# M405B.net
KiCad netlist of a schematic drawn in EAGLE
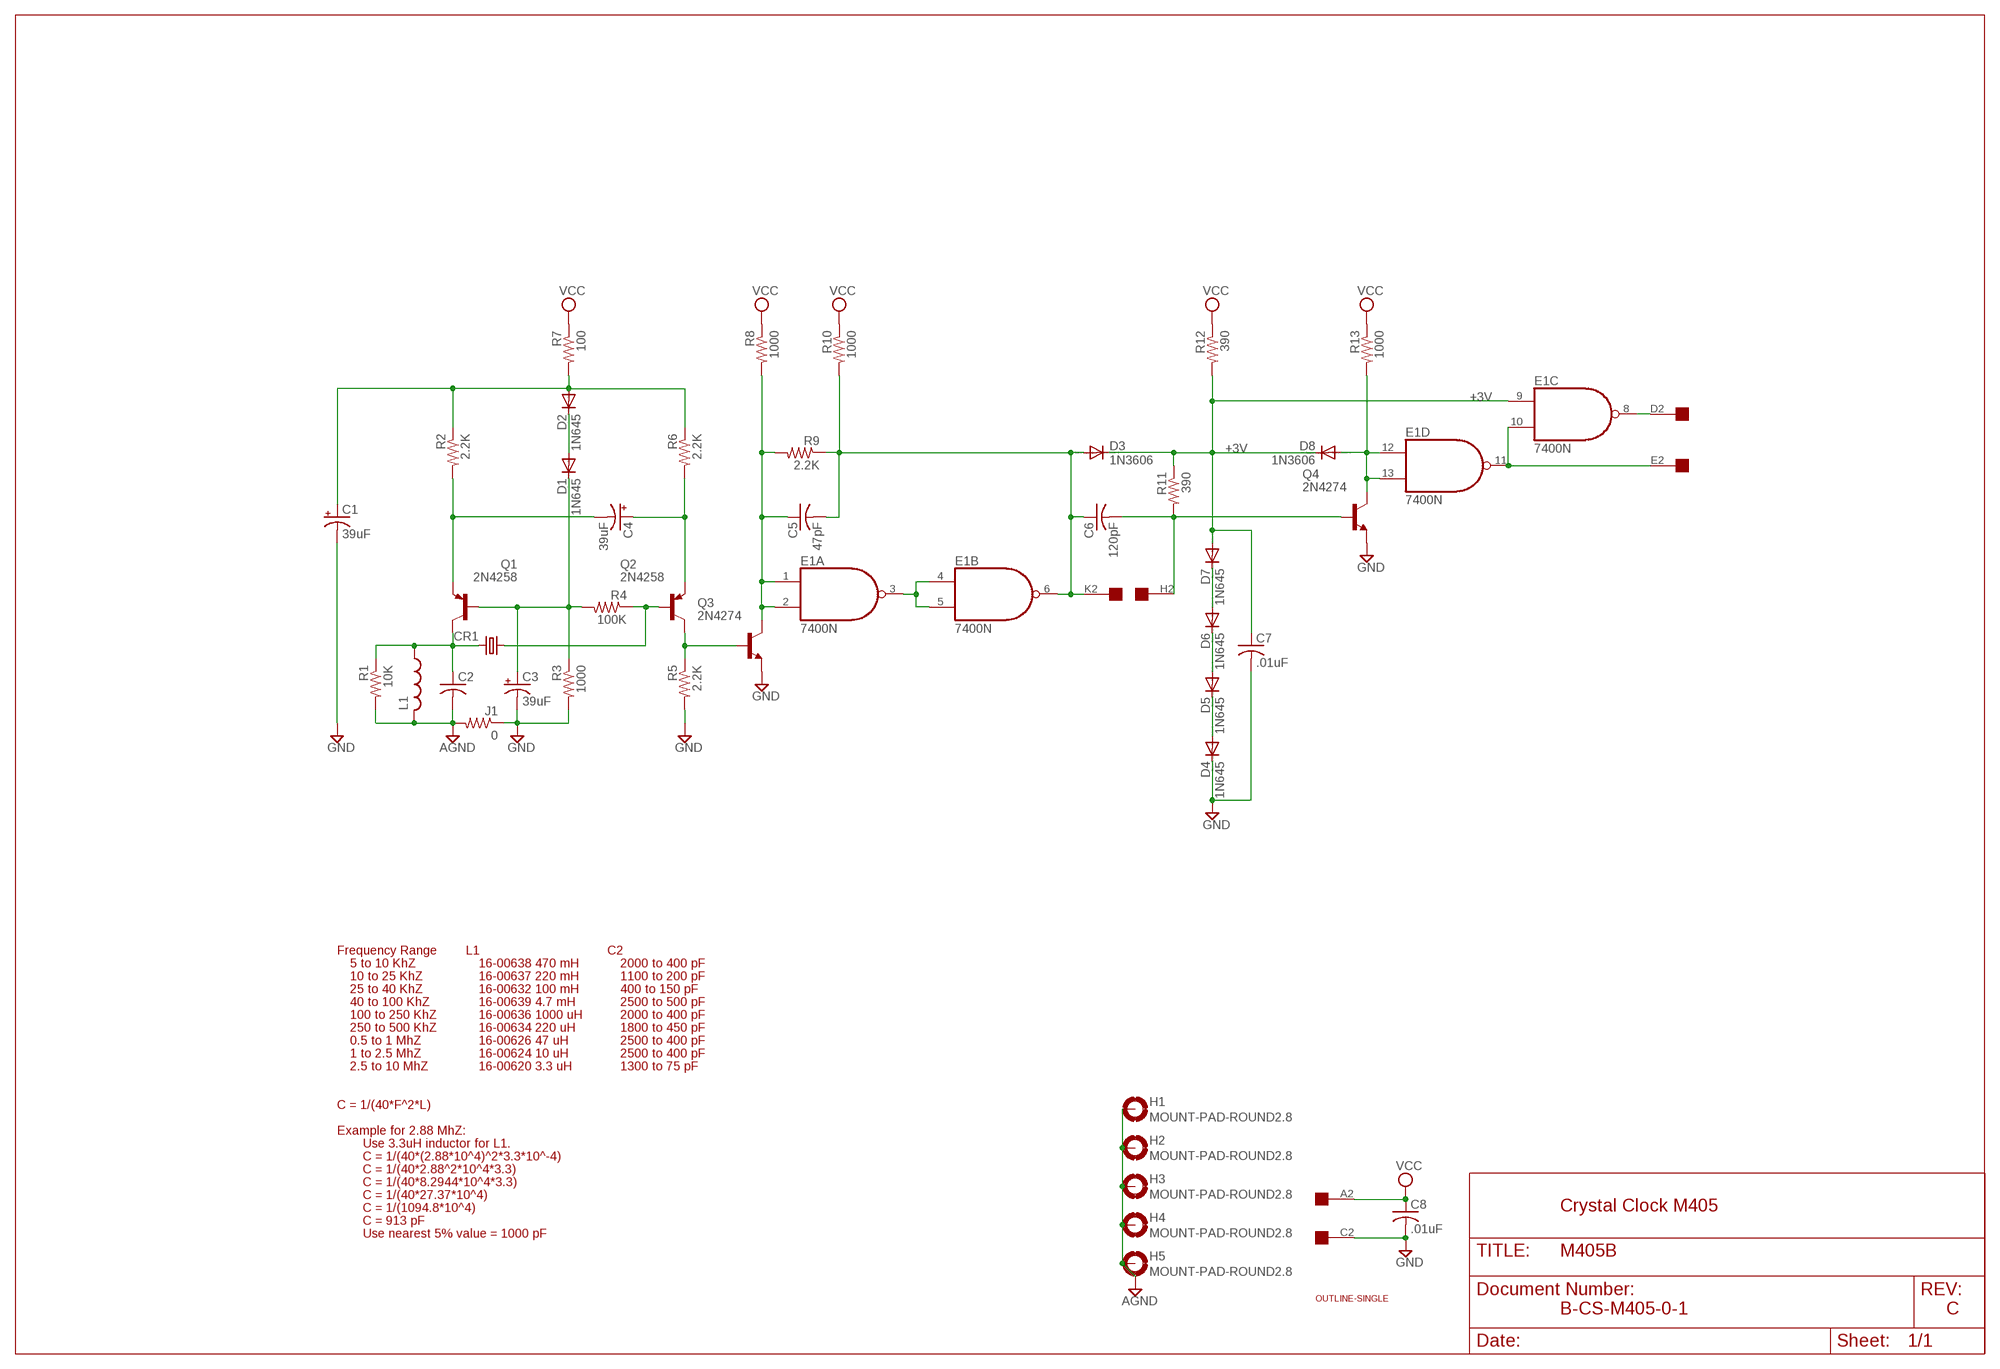
[diagram p0: schematic, sheet 1]

(export (version "E")
  (design (tool "Eeschema 10.0.6"))
  (components
    (comp (ref "C1")
      (value "39uF")
      (footprint "eagle-import:E15-5")
      (libsource (lib "eagle-import") (part "CPOL-USE15-5AXIAL"))
    )
    (comp (ref "C2")
      (value "C-US150-054X183")
      (footprint "eagle-import:C150-054X183")
      (libsource (lib "eagle-import") (part "C-US150-054X183"))
    )
    (comp (ref "C3")
      (value "39uF")
      (footprint "eagle-import:E15-5")
      (libsource (lib "eagle-import") (part "CPOL-USE15-5AXIAL"))
    )
    (comp (ref "C4")
      (value "39uF")
      (footprint "eagle-import:E15-5")
      (libsource (lib "eagle-import") (part "CPOL-USE15-5AXIAL"))
    )
    (comp (ref "C5")
      (value "47pF")
      (footprint "eagle-import:C050-025X075")
      (libsource (lib "eagle-import") (part "C-US050-025X075"))
    )
    (comp (ref "C6")
      (value "120pF")
      (footprint "eagle-import:C050-025X075")
      (libsource (lib "eagle-import") (part "C-US050-025X075"))
    )
    (comp (ref "C7")
      (value ".01uF")
      (footprint "eagle-import:C050-025X075")
      (libsource (lib "eagle-import") (part "C-US050-025X075"))
    )
    (comp (ref "C8")
      (value ".01uF")
      (footprint "eagle-import:C050-025X075")
      (libsource (lib "eagle-import") (part "C-US050-025X075"))
    )
    (comp (ref "CR1")
      (value "CRYSTALHC13U-H")
      (footprint "eagle-import:HC13U-H")
      (libsource (lib "eagle-import") (part "CRYSTALHC13U-H"))
    )
    (comp (ref "D1")
      (value "1N645")
      (footprint "eagle-import:DO35-10")
      (libsource (lib "eagle-import") (part "1N4148DO35-10"))
    )
    (comp (ref "D2")
      (value "1N645")
      (footprint "eagle-import:DO35-10")
      (libsource (lib "eagle-import") (part "1N4148DO35-10"))
    )
    (comp (ref "D3")
      (value "1N3606")
      (footprint "eagle-import:DO35-10")
      (libsource (lib "eagle-import") (part "1N4148DO35-10"))
    )
    (comp (ref "D4")
      (value "1N645")
      (footprint "eagle-import:DO35-10")
      (libsource (lib "eagle-import") (part "1N4148DO35-10"))
    )
    (comp (ref "D5")
      (value "1N645")
      (footprint "eagle-import:DO35-10")
      (libsource (lib "eagle-import") (part "1N4148DO35-10"))
    )
    (comp (ref "D6")
      (value "1N645")
      (footprint "eagle-import:DO35-10")
      (libsource (lib "eagle-import") (part "1N4148DO35-10"))
    )
    (comp (ref "D7")
      (value "1N645")
      (footprint "eagle-import:DO35-10")
      (libsource (lib "eagle-import") (part "1N4148DO35-10"))
    )
    (comp (ref "D8")
      (value "1N3606")
      (footprint "eagle-import:DO35-10")
      (libsource (lib "eagle-import") (part "1N4148DO35-10"))
    )
    (comp (ref "E1")
      (value "7400N")
      (footprint "eagle-import:DIL14")
      (libsource (lib "eagle-import") (part "7400N"))
    )
    (comp (ref "H1")
      (value "MOUNT-PAD-ROUND2.8")
      (footprint "eagle-import:2,8-PAD")
      (libsource (lib "eagle-import") (part "MOUNT-PAD-ROUND2.8"))
    )
    (comp (ref "H2")
      (value "MOUNT-PAD-ROUND2.8")
      (footprint "eagle-import:2,8-PAD")
      (libsource (lib "eagle-import") (part "MOUNT-PAD-ROUND2.8"))
    )
    (comp (ref "H3")
      (value "MOUNT-PAD-ROUND2.8")
      (footprint "eagle-import:2,8-PAD")
      (libsource (lib "eagle-import") (part "MOUNT-PAD-ROUND2.8"))
    )
    (comp (ref "H4")
      (value "MOUNT-PAD-ROUND2.8")
      (footprint "eagle-import:2,8-PAD")
      (libsource (lib "eagle-import") (part "MOUNT-PAD-ROUND2.8"))
    )
    (comp (ref "H5")
      (value "MOUNT-PAD-ROUND2.8")
      (footprint "eagle-import:2,8-PAD")
      (libsource (lib "eagle-import") (part "MOUNT-PAD-ROUND2.8"))
    )
    (comp (ref "J1")
      (value "0")
      (footprint "eagle-import:0207_10")
      (libsource (lib "eagle-import") (part "R-US_0207/10"))
    )
    (comp (ref "L1")
      (value "L-US0207/12")
      (footprint "eagle-import:0207_12")
      (libsource (lib "eagle-import") (part "L-US0207/12"))
    )
    (comp (ref "Q1")
      (value "2N4258")
      (footprint "eagle-import:TO39")
      (libsource (lib "eagle-import") (part "-PNP-TO39-EBC2N3637"))
    )
    (comp (ref "Q2")
      (value "2N4258")
      (footprint "eagle-import:TO39")
      (libsource (lib "eagle-import") (part "-PNP-TO39-EBC2N3637"))
    )
    (comp (ref "Q3")
      (value "2N4274")
      (footprint "eagle-import:TO39")
      (libsource (lib "eagle-import") (part "-NPN-TO39-EBC2N3019"))
    )
    (comp (ref "Q4")
      (value "2N4274")
      (footprint "eagle-import:TO39")
      (libsource (lib "eagle-import") (part "-NPN-TO39-EBC2N3019"))
    )
    (comp (ref "R1")
      (value "10K")
      (footprint "eagle-import:0207_10")
      (libsource (lib "eagle-import") (part "R-US_0207/10"))
    )
    (comp (ref "R2")
      (value "2.2K")
      (footprint "eagle-import:0207_10")
      (libsource (lib "eagle-import") (part "R-US_0207/10"))
    )
    (comp (ref "R3")
      (value "1000")
      (footprint "eagle-import:0207_10")
      (libsource (lib "eagle-import") (part "R-US_0207/10"))
    )
    (comp (ref "R4")
      (value "100K")
      (footprint "eagle-import:0207_10")
      (libsource (lib "eagle-import") (part "R-US_0207/10"))
    )
    (comp (ref "R5")
      (value "2.2K")
      (footprint "eagle-import:0207_10")
      (libsource (lib "eagle-import") (part "R-US_0207/10"))
    )
    (comp (ref "R6")
      (value "2.2K")
      (footprint "eagle-import:0207_10")
      (libsource (lib "eagle-import") (part "R-US_0207/10"))
    )
    (comp (ref "R7")
      (value "100")
      (footprint "eagle-import:0207_10")
      (libsource (lib "eagle-import") (part "R-US_0207/10"))
    )
    (comp (ref "R8")
      (value "1000")
      (footprint "eagle-import:0207_10")
      (libsource (lib "eagle-import") (part "R-US_0207/10"))
    )
    (comp (ref "R9")
      (value "2.2K")
      (footprint "eagle-import:0207_10")
      (libsource (lib "eagle-import") (part "R-US_0207/10"))
    )
    (comp (ref "R10")
      (value "1000")
      (footprint "eagle-import:0207_10")
      (libsource (lib "eagle-import") (part "R-US_0207/10"))
    )
    (comp (ref "R11")
      (value "390")
      (footprint "eagle-import:0207_10")
      (libsource (lib "eagle-import") (part "R-US_0207/10"))
    )
    (comp (ref "R12")
      (value "390")
      (footprint "eagle-import:0207_10")
      (libsource (lib "eagle-import") (part "R-US_0207/10"))
    )
    (comp (ref "R13")
      (value "1000")
      (footprint "eagle-import:0207_10")
      (libsource (lib "eagle-import") (part "R-US_0207/10"))
    )
    (comp (ref "U$1")
      (value "OUTLINE-SINGLE")
      (footprint "eagle-import:SINGLE")
      (libsource (lib "eagle-import") (part "OUTLINE-SINGLE"))
    )
    (comp (ref "U$2")
      (value "EDGE-1")
      (footprint "eagle-import:EDGE-CON1")
      (libsource (lib "eagle-import") (part "EDGE-1"))
    )
  )
  (nets
    (net (code "1") (name "/+3V") (class "Default")
      (node (ref "C7") (pin "1") (pinfunction "1_1") (pintype "passive"))
      (node (ref "D3") (pin "C") (pinfunction "C_C") (pintype "passive"))
      (node (ref "D7") (pin "A") (pinfunction "A_A") (pintype "passive"))
      (node (ref "D8") (pin "C") (pinfunction "C_C") (pintype "passive"))
      (node (ref "E1") (pin "9") (pinfunction "I0_9") (pintype "input"))
      (node (ref "R11") (pin "1") (pinfunction "1_1") (pintype "passive"))
      (node (ref "R12") (pin "2") (pinfunction "2_2") (pintype "passive"))
    )
    (net (code "2") (name "AGND") (class "Default")
      (node (ref "C2") (pin "2") (pinfunction "2_2") (pintype "passive"))
      (node (ref "H1") (pin "B2,8") (pinfunction "MOUNT_B2,8") (pintype "passive"))
      (node (ref "H2") (pin "B2,8") (pinfunction "MOUNT_B2,8") (pintype "passive"))
      (node (ref "H3") (pin "B2,8") (pinfunction "MOUNT_B2,8") (pintype "passive"))
      (node (ref "H4") (pin "B2,8") (pinfunction "MOUNT_B2,8") (pintype "passive"))
      (node (ref "H5") (pin "B2,8") (pinfunction "MOUNT_B2,8") (pintype "passive"))
      (node (ref "J1") (pin "2") (pinfunction "2_2") (pintype "passive"))
      (node (ref "L1") (pin "2") (pinfunction "2_2") (pintype "passive"))
      (node (ref "R1") (pin "2") (pinfunction "2_2") (pintype "passive"))
    )
    (net (code "3") (name "GND") (class "Default")
      (node (ref "C1") (pin "-") (pinfunction "-_-") (pintype "passive"))
      (node (ref "C3") (pin "-") (pinfunction "-_-") (pintype "passive"))
      (node (ref "C7") (pin "2") (pinfunction "2_2") (pintype "passive"))
      (node (ref "C8") (pin "2") (pinfunction "2_2") (pintype "passive"))
      (node (ref "D4") (pin "C") (pinfunction "C_C") (pintype "passive"))
      (node (ref "J1") (pin "1") (pinfunction "1_1") (pintype "passive"))
      (node (ref "Q3") (pin "1") (pinfunction "E_1") (pintype "passive"))
      (node (ref "Q4") (pin "1") (pinfunction "E_1") (pintype "passive"))
      (node (ref "R3") (pin "2") (pinfunction "2_2") (pintype "passive"))
      (node (ref "R5") (pin "2") (pinfunction "2_2") (pintype "passive"))
      (node (ref "U$2") (pin "C2") (pinfunction "1_C2") (pintype "bidirectional"))
    )
    (net (code "4") (name "Net-(C1-Pad+)") (class "Default")
      (node (ref "C1") (pin "+") (pinfunction "+_+") (pintype "passive"))
      (node (ref "D2") (pin "A") (pinfunction "A_A") (pintype "passive"))
      (node (ref "R2") (pin "1") (pinfunction "1_1") (pintype "passive"))
      (node (ref "R6") (pin "1") (pinfunction "1_1") (pintype "passive"))
      (node (ref "R7") (pin "2") (pinfunction "2_2") (pintype "passive"))
    )
    (net (code "5") (name "Net-(D1-PadA)") (class "Default")
      (node (ref "D1") (pin "A") (pinfunction "A_A") (pintype "passive"))
      (node (ref "D2") (pin "C") (pinfunction "C_C") (pintype "passive"))
    )
    (net (code "6") (name "Net-(D4-PadA)") (class "Default")
      (node (ref "D4") (pin "A") (pinfunction "A_A") (pintype "passive"))
      (node (ref "D5") (pin "C") (pinfunction "C_C") (pintype "passive"))
    )
    (net (code "7") (name "Net-(D5-PadA)") (class "Default")
      (node (ref "D5") (pin "A") (pinfunction "A_A") (pintype "passive"))
      (node (ref "D6") (pin "C") (pinfunction "C_C") (pintype "passive"))
    )
    (net (code "8") (name "Net-(D6-PadA)") (class "Default")
      (node (ref "D6") (pin "A") (pinfunction "A_A") (pintype "passive"))
      (node (ref "D7") (pin "C") (pinfunction "C_C") (pintype "passive"))
    )
    (net (code "9") (name "Net-(E1A-I0)") (class "Default")
      (node (ref "C5") (pin "1") (pinfunction "1_1") (pintype "passive"))
      (node (ref "E1") (pin "1") (pinfunction "I0_1") (pintype "input"))
      (node (ref "E1") (pin "2") (pinfunction "I1_2") (pintype "input"))
      (node (ref "Q3") (pin "3") (pinfunction "C_3") (pintype "passive"))
      (node (ref "R8") (pin "2") (pinfunction "2_2") (pintype "passive"))
      (node (ref "R9") (pin "2") (pinfunction "2_2") (pintype "passive"))
    )
    (net (code "10") (name "Net-(E1A-O)") (class "Default")
      (node (ref "E1") (pin "3") (pinfunction "O_3") (pintype "output"))
      (node (ref "E1") (pin "4") (pinfunction "I0_4") (pintype "input"))
      (node (ref "E1") (pin "5") (pinfunction "I1_5") (pintype "input"))
    )
    (net (code "11") (name "Net-(E1B-O)") (class "Default")
      (node (ref "C5") (pin "2") (pinfunction "2_2") (pintype "passive"))
      (node (ref "C6") (pin "1") (pinfunction "1_1") (pintype "passive"))
      (node (ref "D3") (pin "A") (pinfunction "A_A") (pintype "passive"))
      (node (ref "E1") (pin "6") (pinfunction "O_6") (pintype "output"))
      (node (ref "R10") (pin "2") (pinfunction "2_2") (pintype "passive"))
      (node (ref "R9") (pin "1") (pinfunction "1_1") (pintype "passive"))
      (node (ref "U$2") (pin "K2") (pinfunction "1_K2") (pintype "bidirectional"))
    )
    (net (code "12") (name "Net-(E1C-I1)") (class "Default")
      (node (ref "E1") (pin "10") (pinfunction "I1_10") (pintype "input"))
      (node (ref "E1") (pin "11") (pinfunction "O_11") (pintype "output"))
      (node (ref "U$2") (pin "E2") (pinfunction "1_E2") (pintype "bidirectional"))
    )
    (net (code "13") (name "Net-(E1C-O)") (class "Default")
      (node (ref "E1") (pin "8") (pinfunction "O_8") (pintype "output"))
      (node (ref "U$2") (pin "D2") (pinfunction "1_D2") (pintype "bidirectional"))
    )
    (net (code "14") (name "Net-(E1D-I0)") (class "Default")
      (node (ref "D8") (pin "A") (pinfunction "A_A") (pintype "passive"))
      (node (ref "E1") (pin "12") (pinfunction "I0_12") (pintype "input"))
      (node (ref "E1") (pin "13") (pinfunction "I1_13") (pintype "input"))
      (node (ref "Q4") (pin "3") (pinfunction "C_3") (pintype "passive"))
      (node (ref "R13") (pin "2") (pinfunction "2_2") (pintype "passive"))
    )
    (net (code "15") (name "Net-(Q1-B)") (class "Default")
      (node (ref "C3") (pin "+") (pinfunction "+_+") (pintype "passive"))
      (node (ref "D1") (pin "C") (pinfunction "C_C") (pintype "passive"))
      (node (ref "Q1") (pin "2") (pinfunction "B_2") (pintype "passive"))
      (node (ref "R3") (pin "1") (pinfunction "1_1") (pintype "passive"))
      (node (ref "R4") (pin "2") (pinfunction "2_2") (pintype "passive"))
    )
    (net (code "16") (name "Net-(Q1-C)") (class "Default")
      (node (ref "C2") (pin "1") (pinfunction "1_1") (pintype "passive"))
      (node (ref "CR1") (pin "2") (pinfunction "2_2") (pintype "passive"))
      (node (ref "L1") (pin "1") (pinfunction "1_1") (pintype "passive"))
      (node (ref "Q1") (pin "3") (pinfunction "C_3") (pintype "passive"))
      (node (ref "R1") (pin "1") (pinfunction "1_1") (pintype "passive"))
    )
    (net (code "17") (name "Net-(Q1-E)") (class "Default")
      (node (ref "C4") (pin "-") (pinfunction "-_-") (pintype "passive"))
      (node (ref "Q1") (pin "1") (pinfunction "E_1") (pintype "passive"))
      (node (ref "R2") (pin "2") (pinfunction "2_2") (pintype "passive"))
    )
    (net (code "18") (name "Net-(Q2-B)") (class "Default")
      (node (ref "CR1") (pin "1") (pinfunction "1_1") (pintype "passive"))
      (node (ref "Q2") (pin "2") (pinfunction "B_2") (pintype "passive"))
      (node (ref "R4") (pin "1") (pinfunction "1_1") (pintype "passive"))
    )
    (net (code "19") (name "Net-(Q2-C)") (class "Default")
      (node (ref "Q2") (pin "3") (pinfunction "C_3") (pintype "passive"))
      (node (ref "Q3") (pin "2") (pinfunction "B_2") (pintype "passive"))
      (node (ref "R5") (pin "1") (pinfunction "1_1") (pintype "passive"))
    )
    (net (code "20") (name "Net-(Q2-E)") (class "Default")
      (node (ref "C4") (pin "+") (pinfunction "+_+") (pintype "passive"))
      (node (ref "Q2") (pin "1") (pinfunction "E_1") (pintype "passive"))
      (node (ref "R6") (pin "2") (pinfunction "2_2") (pintype "passive"))
    )
    (net (code "21") (name "Net-(Q4-B)") (class "Default")
      (node (ref "C6") (pin "2") (pinfunction "2_2") (pintype "passive"))
      (node (ref "Q4") (pin "2") (pinfunction "B_2") (pintype "passive"))
      (node (ref "R11") (pin "2") (pinfunction "2_2") (pintype "passive"))
      (node (ref "U$2") (pin "H2") (pinfunction "1_H2") (pintype "bidirectional"))
    )
    (net (code "22") (name "VCC") (class "Default")
      (node (ref "C8") (pin "1") (pinfunction "1_1") (pintype "passive"))
      (node (ref "R10") (pin "1") (pinfunction "1_1") (pintype "passive"))
      (node (ref "R12") (pin "1") (pinfunction "1_1") (pintype "passive"))
      (node (ref "R13") (pin "1") (pinfunction "1_1") (pintype "passive"))
      (node (ref "R7") (pin "1") (pinfunction "1_1") (pintype "passive"))
      (node (ref "R8") (pin "1") (pinfunction "1_1") (pintype "passive"))
      (node (ref "U$2") (pin "A2") (pinfunction "1_A2") (pintype "bidirectional"))
    )
  )
)
